# d1mini-sw.net
KiCad netlist of a schematic drawn in EAGLE
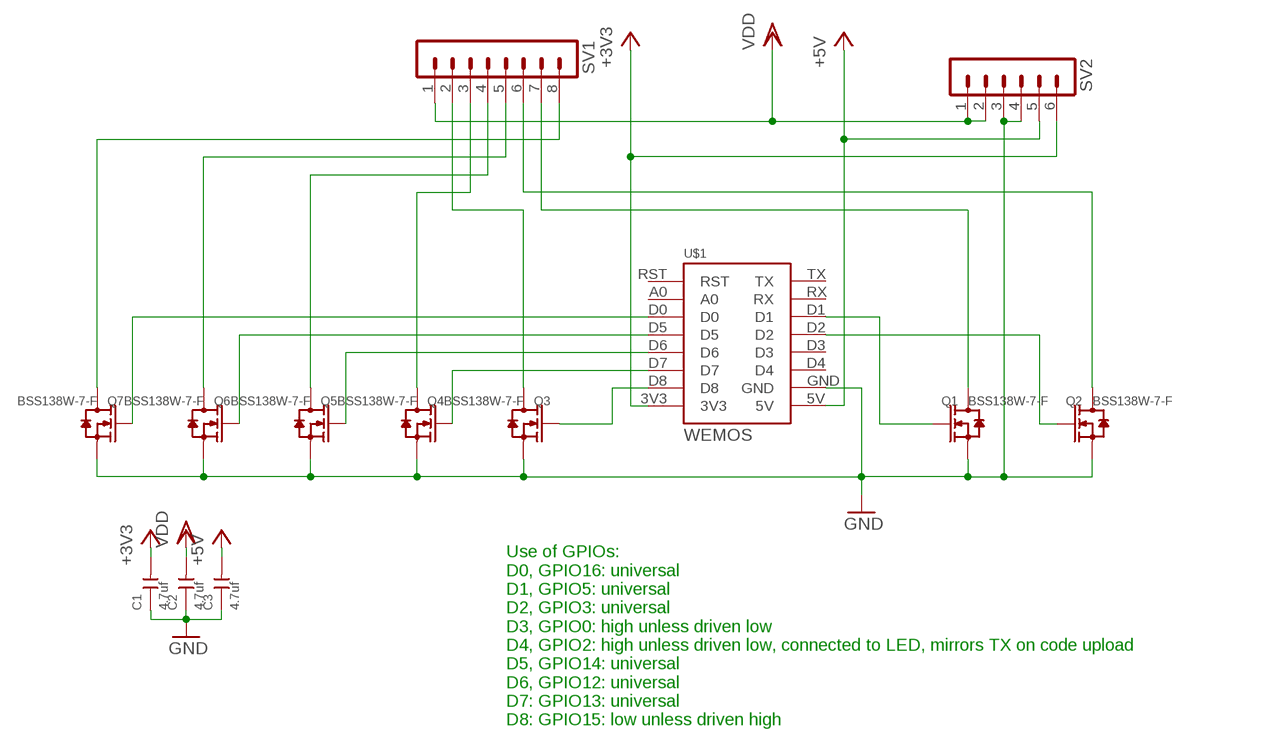
[diagram p0: schematic, sheet 1]

(export (version "E")
  (design (tool "Eeschema 10.0.6"))
  (components
    (comp (ref "C1")
      (value "4.7uf")
      (footprint "eagle-import:C0805")
      (fields (field (name "MPN") "CC0805KKX5R8BB475"))
      (libsource (lib "eagle-import") (part "CERAMIC-4.7UF-25V-10%-X5R(0805)"))
    )
    (comp (ref "C2")
      (value "4.7uf")
      (footprint "eagle-import:C0805")
      (fields (field (name "MPN") "CC0805KKX5R8BB475"))
      (libsource (lib "eagle-import") (part "CERAMIC-4.7UF-25V-10%-X5R(0805)"))
    )
    (comp (ref "C3")
      (value "4.7uf")
      (footprint "eagle-import:C0805")
      (fields (field (name "MPN") "CC0805KKX5R8BB475"))
      (libsource (lib "eagle-import") (part "CERAMIC-4.7UF-25V-10%-X5R(0805)"))
    )
    (comp (ref "Q1")
      (value "BSS138W-7-F")
      (footprint "eagle-import:SOT-23")
      (libsource (lib "eagle-import") (part "SMD-MOSFET-N-CH-50V-200MA-BSS138W-7-F(SOT-23)"))
    )
    (comp (ref "Q2")
      (value "BSS138W-7-F")
      (footprint "eagle-import:SOT-23")
      (libsource (lib "eagle-import") (part "SMD-MOSFET-N-CH-50V-200MA-BSS138W-7-F(SOT-23)"))
    )
    (comp (ref "Q3")
      (value "BSS138W-7-F")
      (footprint "eagle-import:SOT-23")
      (libsource (lib "eagle-import") (part "SMD-MOSFET-N-CH-50V-200MA-BSS138W-7-F(SOT-23)"))
    )
    (comp (ref "Q4")
      (value "BSS138W-7-F")
      (footprint "eagle-import:SOT-23")
      (libsource (lib "eagle-import") (part "SMD-MOSFET-N-CH-50V-200MA-BSS138W-7-F(SOT-23)"))
    )
    (comp (ref "Q5")
      (value "BSS138W-7-F")
      (footprint "eagle-import:SOT-23")
      (libsource (lib "eagle-import") (part "SMD-MOSFET-N-CH-50V-200MA-BSS138W-7-F(SOT-23)"))
    )
    (comp (ref "Q6")
      (value "BSS138W-7-F")
      (footprint "eagle-import:SOT-23")
      (libsource (lib "eagle-import") (part "SMD-MOSFET-N-CH-50V-200MA-BSS138W-7-F(SOT-23)"))
    )
    (comp (ref "Q7")
      (value "BSS138W-7-F")
      (footprint "eagle-import:SOT-23")
      (libsource (lib "eagle-import") (part "SMD-MOSFET-N-CH-50V-200MA-BSS138W-7-F(SOT-23)"))
    )
    (comp (ref "SV1")
      (value "MA08-1")
      (footprint "eagle-import:MA08-1")
      (libsource (lib "eagle-import") (part "MA08-1"))
    )
    (comp (ref "SV2")
      (value "MA06-1")
      (footprint "eagle-import:MA06-1")
      (libsource (lib "eagle-import") (part "MA06-1"))
    )
    (comp (ref "U$1")
      (value "WEMOS")
      (footprint "eagle-import:WEMOS")
      (libsource (lib "eagle-import") (part "WEMOS"))
    )
  )
  (nets
    (net (code "1") (name "+3V3") (class "Default")
      (node (ref "C1") (pin "2") (pinfunction "2_2") (pintype "passive"))
      (node (ref "SV2") (pin "6") (pinfunction "6_6") (pintype "passive"))
      (node (ref "U$1") (pin "3V3") (pinfunction "3V3_3V3") (pintype "bidirectional"))
    )
    (net (code "2") (name "+5V") (class "Default")
      (node (ref "C3") (pin "2") (pinfunction "2_2") (pintype "passive"))
      (node (ref "SV2") (pin "5") (pinfunction "5_5") (pintype "passive"))
      (node (ref "U$1") (pin "5V") (pinfunction "5V_5V") (pintype "bidirectional"))
    )
    (net (code "3") (name "GND") (class "Default")
      (node (ref "C1") (pin "1") (pinfunction "1_1") (pintype "passive"))
      (node (ref "C2") (pin "1") (pinfunction "1_1") (pintype "passive"))
      (node (ref "C3") (pin "1") (pinfunction "1_1") (pintype "passive"))
      (node (ref "Q1") (pin "2") (pinfunction "S_2") (pintype "passive"))
      (node (ref "Q2") (pin "2") (pinfunction "S_2") (pintype "passive"))
      (node (ref "Q3") (pin "2") (pinfunction "S_2") (pintype "passive"))
      (node (ref "Q4") (pin "2") (pinfunction "S_2") (pintype "passive"))
      (node (ref "Q5") (pin "2") (pinfunction "S_2") (pintype "passive"))
      (node (ref "Q6") (pin "2") (pinfunction "S_2") (pintype "passive"))
      (node (ref "Q7") (pin "2") (pinfunction "S_2") (pintype "passive"))
      (node (ref "SV2") (pin "3") (pinfunction "3_3") (pintype "passive"))
      (node (ref "SV2") (pin "4") (pinfunction "4_4") (pintype "passive"))
      (node (ref "U$1") (pin "GND") (pinfunction "GND_GND") (pintype "bidirectional"))
    )
    (net (code "4") (name "Net-(Q1-D)") (class "Default")
      (node (ref "Q1") (pin "3") (pinfunction "D_3") (pintype "passive"))
      (node (ref "SV1") (pin "7") (pinfunction "7_7") (pintype "passive"))
    )
    (net (code "5") (name "Net-(Q1-G)") (class "Default")
      (node (ref "Q1") (pin "1") (pinfunction "G_1") (pintype "passive"))
      (node (ref "U$1") (pin "D1") (pinfunction "D1_D1") (pintype "bidirectional"))
    )
    (net (code "6") (name "Net-(Q2-D)") (class "Default")
      (node (ref "Q2") (pin "3") (pinfunction "D_3") (pintype "passive"))
      (node (ref "SV1") (pin "6") (pinfunction "6_6") (pintype "passive"))
    )
    (net (code "7") (name "Net-(Q2-G)") (class "Default")
      (node (ref "Q2") (pin "1") (pinfunction "G_1") (pintype "passive"))
      (node (ref "U$1") (pin "D2") (pinfunction "D2_D2") (pintype "bidirectional"))
    )
    (net (code "8") (name "Net-(Q3-D)") (class "Default")
      (node (ref "Q3") (pin "3") (pinfunction "D_3") (pintype "passive"))
      (node (ref "SV1") (pin "2") (pinfunction "2_2") (pintype "passive"))
    )
    (net (code "9") (name "Net-(Q3-G)") (class "Default")
      (node (ref "Q3") (pin "1") (pinfunction "G_1") (pintype "passive"))
      (node (ref "U$1") (pin "D8") (pinfunction "D8_D8") (pintype "bidirectional"))
    )
    (net (code "10") (name "Net-(Q4-D)") (class "Default")
      (node (ref "Q4") (pin "3") (pinfunction "D_3") (pintype "passive"))
      (node (ref "SV1") (pin "3") (pinfunction "3_3") (pintype "passive"))
    )
    (net (code "11") (name "Net-(Q4-G)") (class "Default")
      (node (ref "Q4") (pin "1") (pinfunction "G_1") (pintype "passive"))
      (node (ref "U$1") (pin "D7") (pinfunction "D7_D7") (pintype "bidirectional"))
    )
    (net (code "12") (name "Net-(Q5-D)") (class "Default")
      (node (ref "Q5") (pin "3") (pinfunction "D_3") (pintype "passive"))
      (node (ref "SV1") (pin "4") (pinfunction "4_4") (pintype "passive"))
    )
    (net (code "13") (name "Net-(Q5-G)") (class "Default")
      (node (ref "Q5") (pin "1") (pinfunction "G_1") (pintype "passive"))
      (node (ref "U$1") (pin "D6") (pinfunction "D6_D6") (pintype "bidirectional"))
    )
    (net (code "14") (name "Net-(Q6-D)") (class "Default")
      (node (ref "Q6") (pin "3") (pinfunction "D_3") (pintype "passive"))
      (node (ref "SV1") (pin "5") (pinfunction "5_5") (pintype "passive"))
    )
    (net (code "15") (name "Net-(Q6-G)") (class "Default")
      (node (ref "Q6") (pin "1") (pinfunction "G_1") (pintype "passive"))
      (node (ref "U$1") (pin "D5") (pinfunction "D5_D5") (pintype "bidirectional"))
    )
    (net (code "16") (name "Net-(Q7-D)") (class "Default")
      (node (ref "Q7") (pin "3") (pinfunction "D_3") (pintype "passive"))
      (node (ref "SV1") (pin "8") (pinfunction "8_8") (pintype "passive"))
    )
    (net (code "17") (name "Net-(Q7-G)") (class "Default")
      (node (ref "Q7") (pin "1") (pinfunction "G_1") (pintype "passive"))
      (node (ref "U$1") (pin "D0") (pinfunction "D0_D0") (pintype "bidirectional"))
    )
    (net (code "18") (name "VDD") (class "Default")
      (node (ref "C2") (pin "2") (pinfunction "2_2") (pintype "passive"))
      (node (ref "SV1") (pin "1") (pinfunction "1_1") (pintype "passive"))
      (node (ref "SV2") (pin "1") (pinfunction "1_1") (pintype "passive"))
      (node (ref "SV2") (pin "2") (pinfunction "2_2") (pintype "passive"))
    )
    (net (code "19") (name "unconnected-(U$1-PadA0)") (class "Default")
      (node (ref "U$1") (pin "A0") (pinfunction "A0_A0") (pintype "bidirectional"))
    )
    (net (code "20") (name "unconnected-(U$1-PadD3)") (class "Default")
      (node (ref "U$1") (pin "D3") (pinfunction "D3_D3") (pintype "bidirectional"))
    )
    (net (code "21") (name "unconnected-(U$1-PadD4)") (class "Default")
      (node (ref "U$1") (pin "D4") (pinfunction "D4_D4") (pintype "bidirectional"))
    )
    (net (code "22") (name "unconnected-(U$1-PadRST)") (class "Default")
      (node (ref "U$1") (pin "RST") (pinfunction "RST_RST") (pintype "bidirectional"))
    )
    (net (code "23") (name "unconnected-(U$1-PadRX)") (class "Default")
      (node (ref "U$1") (pin "RX") (pinfunction "RX_RX") (pintype "bidirectional"))
    )
    (net (code "24") (name "unconnected-(U$1-PadTX)") (class "Default")
      (node (ref "U$1") (pin "TX") (pinfunction "TX_TX") (pintype "bidirectional"))
    )
  )
)
